# Arduino_MEGA_shield.net
KiCad netlist of a schematic drawn in EAGLE
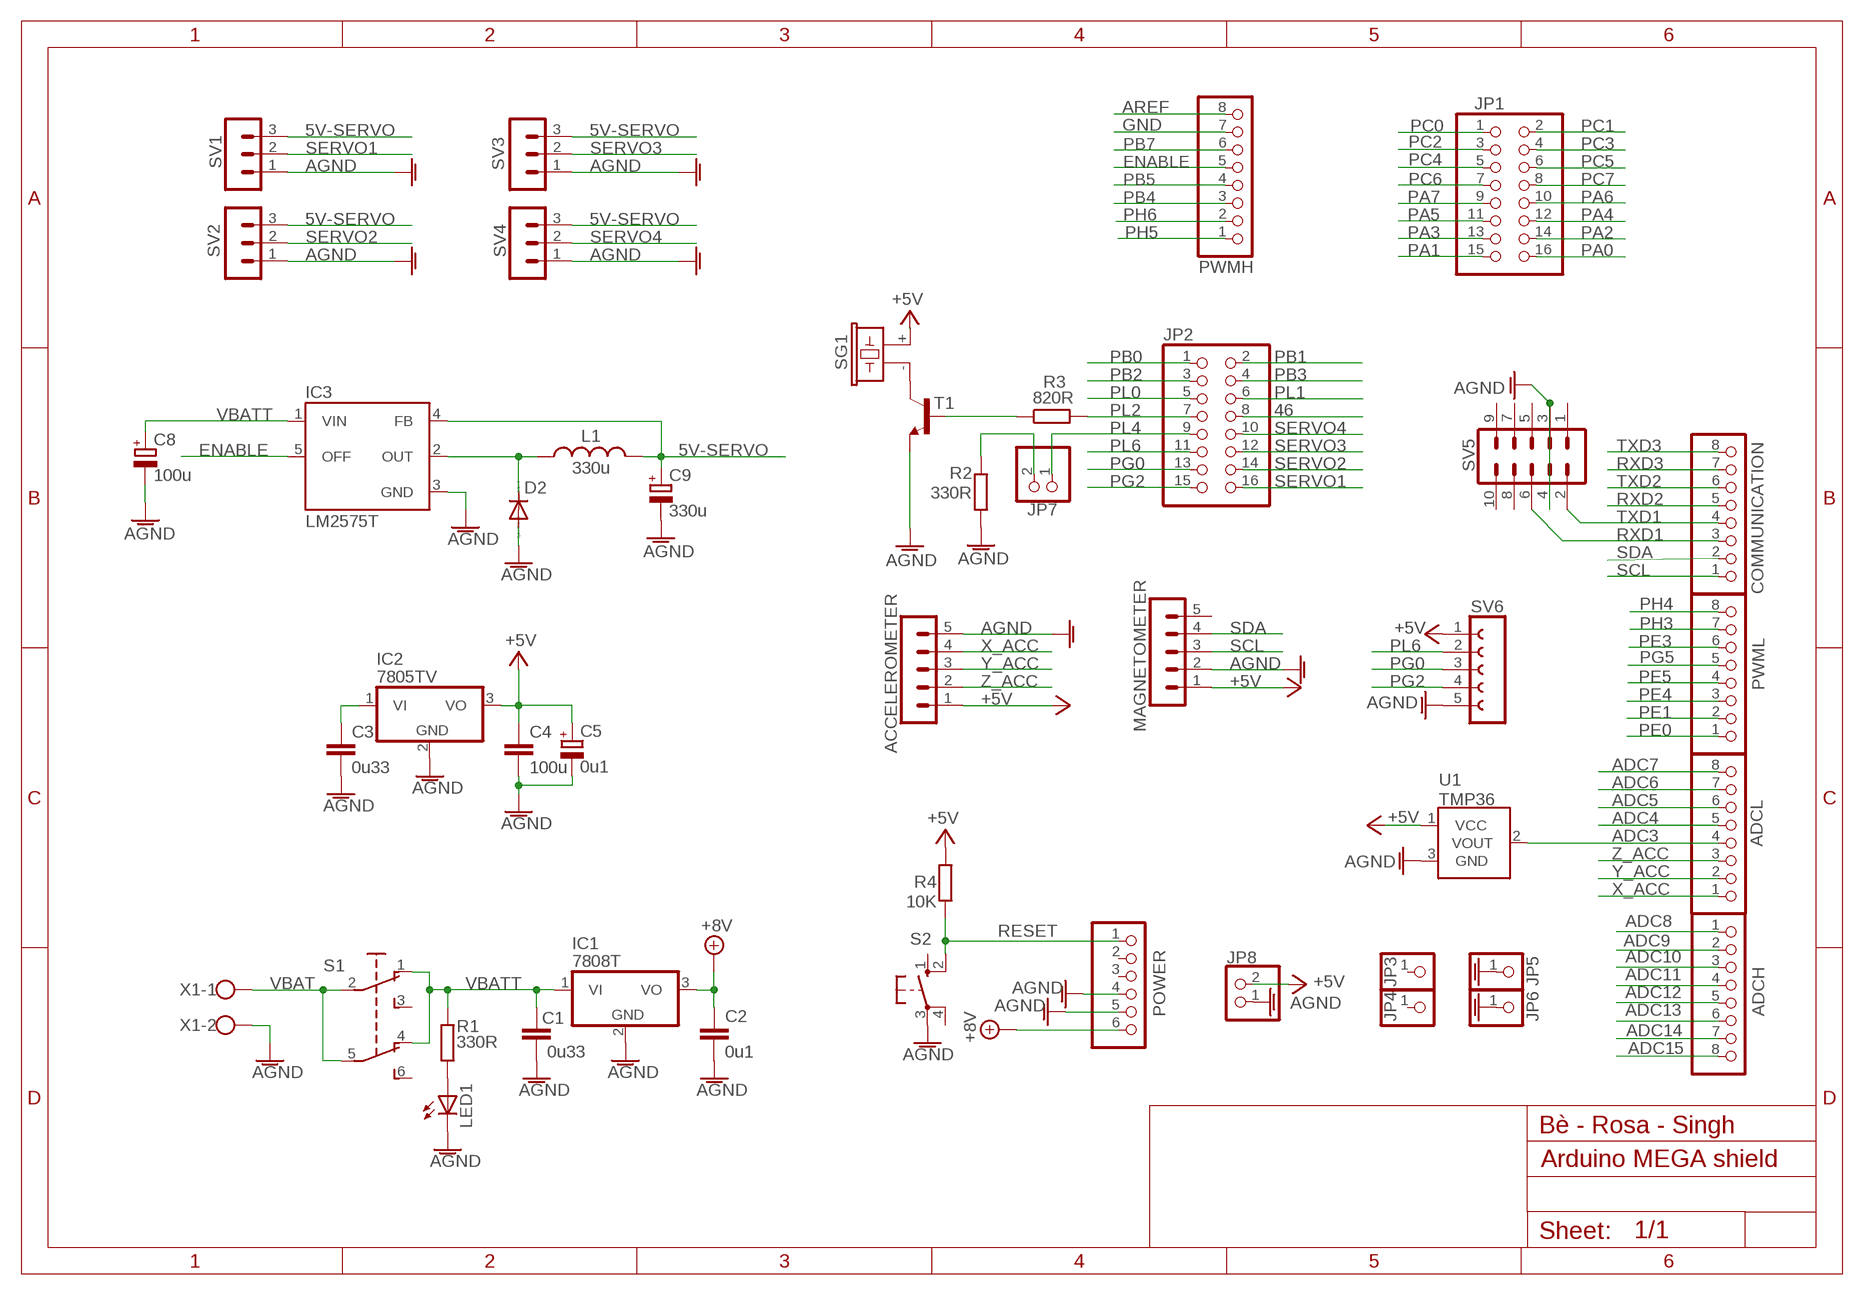
[diagram p0: schematic, sheet 1]

(export (version "E")
  (design (tool "Eeschema 10.0.6"))
  (components
    (comp (ref "ACCELEROMETER")
      (value "MA05-1")
      (footprint "eagle-import:MA05-1")
      (libsource (lib "eagle-import") (part "MA05-1"))
    )
    (comp (ref "ADCH")
      (value "PINHD-1X8")
      (footprint "eagle-import:1X08")
      (libsource (lib "eagle-import") (part "PINHD-1X8"))
    )
    (comp (ref "ADCL")
      (value "PINHD-1X8")
      (footprint "eagle-import:1X08")
      (libsource (lib "eagle-import") (part "PINHD-1X8"))
    )
    (comp (ref "C1")
      (value "0u33")
      (footprint "eagle-import:C050-035X075")
      (libsource (lib "eagle-import") (part "C-EU050-035X075"))
    )
    (comp (ref "C2")
      (value "0u1")
      (footprint "eagle-import:C050-035X075")
      (libsource (lib "eagle-import") (part "C-EU050-035X075"))
    )
    (comp (ref "C3")
      (value "0u33")
      (footprint "eagle-import:C050-035X075")
      (libsource (lib "eagle-import") (part "C-EU050-035X075"))
    )
    (comp (ref "C4")
      (value "100u")
      (footprint "eagle-import:C050-035X075")
      (libsource (lib "eagle-import") (part "C-EU050-035X075"))
    )
    (comp (ref "C5")
      (value "0u1")
      (footprint "eagle-import:E2,5-7")
      (libsource (lib "eagle-import") (part "CPOL-EUE2.5-7"))
    )
    (comp (ref "C8")
      (value "100u")
      (footprint "eagle-import:E3,5-8")
      (libsource (lib "eagle-import") (part "CPOL-EUE3.5-8"))
    )
    (comp (ref "C9")
      (value "330u")
      (footprint "eagle-import:E3,5-8")
      (libsource (lib "eagle-import") (part "CPOL-EUE3.5-8"))
    )
    (comp (ref "COMMUNICATION")
      (value "PINHD-1X8")
      (footprint "eagle-import:1X08")
      (libsource (lib "eagle-import") (part "PINHD-1X8"))
    )
    (comp (ref "D2")
      (value "1N5819")
      (footprint "eagle-import:DO35-10")
      (libsource (lib "eagle-import") (part "BA221"))
    )
    (comp (ref "IC1")
      (value "7808T")
      (footprint "eagle-import:TO220H")
      (libsource (lib "eagle-import") (part "78T08"))
    )
    (comp (ref "IC2")
      (value "7805TV")
      (footprint "eagle-import:TO220V")
      (libsource (lib "eagle-import") (part "78TV05"))
    )
    (comp (ref "IC3")
      (value "LM2575T")
      (footprint "eagle-import:TO220-5")
      (libsource (lib "eagle-import") (part "LM2575T"))
    )
    (comp (ref "JP1")
      (value "PINHD-2X8")
      (footprint "eagle-import:2X08")
      (libsource (lib "eagle-import") (part "PINHD-2X8"))
    )
    (comp (ref "JP2")
      (value "PINHD-2X8")
      (footprint "eagle-import:2X08")
      (libsource (lib "eagle-import") (part "PINHD-2X8"))
    )
    (comp (ref "JP3")
      (value "PINHD-1X1")
      (footprint "eagle-import:1X01")
      (libsource (lib "eagle-import") (part "PINHD-1X1"))
    )
    (comp (ref "JP4")
      (value "PINHD-1X1")
      (footprint "eagle-import:1X01")
      (libsource (lib "eagle-import") (part "PINHD-1X1"))
    )
    (comp (ref "JP5")
      (value "PINHD-1X1")
      (footprint "eagle-import:1X01")
      (libsource (lib "eagle-import") (part "PINHD-1X1"))
    )
    (comp (ref "JP6")
      (value "PINHD-1X1")
      (footprint "eagle-import:1X01")
      (libsource (lib "eagle-import") (part "PINHD-1X1"))
    )
    (comp (ref "JP7")
      (value "PINHD-1X2")
      (footprint "eagle-import:1X02")
      (libsource (lib "eagle-import") (part "PINHD-1X2"))
    )
    (comp (ref "JP8")
      (value "PINHD-1X2")
      (footprint "eagle-import:1X02")
      (libsource (lib "eagle-import") (part "PINHD-1X2"))
    )
    (comp (ref "L1")
      (value "330u")
      (footprint "eagle-import:AXIAL-0.6")
      (libsource (lib "eagle-import") (part "INDUCTORAXIAL-0.6"))
    )
    (comp (ref "LED1")
      (value "LED5MM")
      (footprint "eagle-import:LED5MM")
      (libsource (lib "eagle-import") (part "LED5MM"))
    )
    (comp (ref "MAGNETOMETER")
      (value "MA05-1")
      (footprint "eagle-import:MA05-1")
      (libsource (lib "eagle-import") (part "MA05-1"))
    )
    (comp (ref "POWER")
      (value "PINHD-1X6")
      (footprint "eagle-import:1X06")
      (libsource (lib "eagle-import") (part "PINHD-1X6"))
    )
    (comp (ref "PWMH")
      (value "PINHD-1X8")
      (footprint "eagle-import:1X08")
      (libsource (lib "eagle-import") (part "PINHD-1X8"))
    )
    (comp (ref "PWML")
      (value "PINHD-1X8")
      (footprint "eagle-import:1X08")
      (libsource (lib "eagle-import") (part "PINHD-1X8"))
    )
    (comp (ref "R1")
      (value "330R")
      (footprint "eagle-import:0207_10")
      (libsource (lib "eagle-import") (part "R-EU_0207/10"))
    )
    (comp (ref "R2")
      (value "330R")
      (footprint "eagle-import:0207_10")
      (libsource (lib "eagle-import") (part "R-EU_0207/10"))
    )
    (comp (ref "R3")
      (value "820R")
      (footprint "eagle-import:0207_10")
      (libsource (lib "eagle-import") (part "R-EU_0207/10"))
    )
    (comp (ref "R4")
      (value "10K")
      (footprint "eagle-import:0207_10")
      (libsource (lib "eagle-import") (part "R-EU_0207/10"))
    )
    (comp (ref "S1")
      (value "TL46PO")
      (footprint "eagle-import:TL4XPO")
      (libsource (lib "eagle-import") (part "TL46PO"))
    )
    (comp (ref "S2")
      (value "10-XX")
      (footprint "eagle-import:B3F-10XX")
      (fields (field (name "MPN") "B3F-1000"))
      (libsource (lib "eagle-import") (part "10-XX"))
    )
    (comp (ref "SG1")
      (value "F/CM12P")
      (footprint "eagle-import:F_CM12P")
      (libsource (lib "eagle-import") (part "F/CM12P"))
    )
    (comp (ref "SV1")
      (value "MA03-1")
      (footprint "eagle-import:MA03-1")
      (libsource (lib "eagle-import") (part "MA03-1"))
    )
    (comp (ref "SV2")
      (value "MA03-1")
      (footprint "eagle-import:MA03-1")
      (libsource (lib "eagle-import") (part "MA03-1"))
    )
    (comp (ref "SV3")
      (value "MA03-1")
      (footprint "eagle-import:MA03-1")
      (libsource (lib "eagle-import") (part "MA03-1"))
    )
    (comp (ref "SV4")
      (value "MA03-1")
      (footprint "eagle-import:MA03-1")
      (libsource (lib "eagle-import") (part "MA03-1"))
    )
    (comp (ref "SV5")
      (value "MA05-2")
      (footprint "eagle-import:MA05-2")
      (libsource (lib "eagle-import") (part "MA05-2"))
    )
    (comp (ref "SV6")
      (value "FE05-1")
      (footprint "eagle-import:FE05-1")
      (libsource (lib "eagle-import") (part "FE05-1"))
    )
    (comp (ref "T1")
      (value "BC547A-NPN-TO92-CBE")
      (footprint "eagle-import:TO92-CBE")
      (libsource (lib "eagle-import") (part "-NPN-TO92-CBEBC547A"))
    )
    (comp (ref "U1")
      (value "TMP36")
      (footprint "eagle-import:TO-92")
      (libsource (lib "eagle-import") (part "TMP36GT9"))
    )
    (comp (ref "X1")
      (value "W237-102")
      (footprint "eagle-import:W237-102")
      (fields (field (name "MPN") "237-102"))
      (libsource (lib "eagle-import") (part "W237-102"))
    )
  )
  (nets
    (net (code "1") (name "+5V") (class "Default")
      (node (ref "ACCELEROMETER") (pin "1") (pinfunction "1_1") (pintype "passive"))
      (node (ref "C4") (pin "1") (pinfunction "1_1") (pintype "passive"))
      (node (ref "C5") (pin "+") (pinfunction "+_+") (pintype "passive"))
      (node (ref "IC2") (pin "3") (pinfunction "VO_3") (pintype "passive"))
      (node (ref "JP8") (pin "2") (pinfunction "2_2") (pintype "passive"))
      (node (ref "MAGNETOMETER") (pin "1") (pinfunction "1_1") (pintype "passive"))
      (node (ref "R4") (pin "2") (pinfunction "2_2") (pintype "passive"))
      (node (ref "SG1") (pin "+") (pinfunction "1_+") (pintype "passive"))
      (node (ref "SV6") (pin "1") (pinfunction "1_1") (pintype "passive"))
      (node (ref "U1") (pin "1") (pinfunction "VCC_1") (pintype "bidirectional"))
    )
    (net (code "2") (name "+8V") (class "Default")
      (node (ref "C2") (pin "1") (pinfunction "1_1") (pintype "passive"))
      (node (ref "IC1") (pin "3") (pinfunction "VO_3") (pintype "passive"))
      (node (ref "POWER") (pin "6") (pinfunction "6_6") (pintype "passive"))
    )
    (net (code "3") (name "/5V-SERVO") (class "Default")
      (node (ref "C9") (pin "+") (pinfunction "+_+") (pintype "passive"))
      (node (ref "IC3") (pin "4") (pinfunction "FB_4") (pintype "input"))
      (node (ref "L1") (pin "P$2") (pinfunction "2_P$2") (pintype "passive"))
      (node (ref "SV1") (pin "3") (pinfunction "3_3") (pintype "passive"))
      (node (ref "SV2") (pin "3") (pinfunction "3_3") (pintype "passive"))
      (node (ref "SV3") (pin "3") (pinfunction "3_3") (pintype "passive"))
      (node (ref "SV4") (pin "3") (pinfunction "3_3") (pintype "passive"))
    )
    (net (code "4") (name "/46") (class "Default")
      (node (ref "JP2") (pin "8") (pinfunction "8_8") (pintype "passive"))
    )
    (net (code "5") (name "/ADC3") (class "Default")
      (node (ref "ADCL") (pin "4") (pinfunction "4_4") (pintype "passive"))
      (node (ref "U1") (pin "2") (pinfunction "VOUT_2") (pintype "bidirectional"))
    )
    (net (code "6") (name "/ADC4") (class "Default")
      (node (ref "ADCL") (pin "5") (pinfunction "5_5") (pintype "passive"))
    )
    (net (code "7") (name "/ADC5") (class "Default")
      (node (ref "ADCL") (pin "6") (pinfunction "6_6") (pintype "passive"))
    )
    (net (code "8") (name "/ADC6") (class "Default")
      (node (ref "ADCL") (pin "7") (pinfunction "7_7") (pintype "passive"))
    )
    (net (code "9") (name "/ADC7") (class "Default")
      (node (ref "ADCL") (pin "8") (pinfunction "8_8") (pintype "passive"))
    )
    (net (code "10") (name "/ADC8") (class "Default")
      (node (ref "ADCH") (pin "1") (pinfunction "1_1") (pintype "passive"))
    )
    (net (code "11") (name "/ADC9") (class "Default")
      (node (ref "ADCH") (pin "2") (pinfunction "2_2") (pintype "passive"))
    )
    (net (code "12") (name "/ADC10") (class "Default")
      (node (ref "ADCH") (pin "3") (pinfunction "3_3") (pintype "passive"))
    )
    (net (code "13") (name "/ADC11") (class "Default")
      (node (ref "ADCH") (pin "4") (pinfunction "4_4") (pintype "passive"))
    )
    (net (code "14") (name "/ADC12") (class "Default")
      (node (ref "ADCH") (pin "5") (pinfunction "5_5") (pintype "passive"))
    )
    (net (code "15") (name "/ADC13") (class "Default")
      (node (ref "ADCH") (pin "6") (pinfunction "6_6") (pintype "passive"))
    )
    (net (code "16") (name "/ADC14") (class "Default")
      (node (ref "ADCH") (pin "7") (pinfunction "7_7") (pintype "passive"))
    )
    (net (code "17") (name "/ADC15") (class "Default")
      (node (ref "ADCH") (pin "8") (pinfunction "8_8") (pintype "passive"))
    )
    (net (code "18") (name "/AREF") (class "Default")
      (node (ref "PWMH") (pin "8") (pinfunction "8_8") (pintype "passive"))
    )
    (net (code "19") (name "/ENABLE") (class "Default")
      (node (ref "IC3") (pin "5") (pinfunction "OFF_5") (pintype "input"))
      (node (ref "PWMH") (pin "5") (pinfunction "5_5") (pintype "passive"))
    )
    (net (code "20") (name "/GND") (class "Default")
      (node (ref "PWMH") (pin "7") (pinfunction "7_7") (pintype "passive"))
    )
    (net (code "21") (name "/PA0") (class "Default")
      (node (ref "JP1") (pin "16") (pinfunction "16_16") (pintype "passive"))
    )
    (net (code "22") (name "/PA1") (class "Default")
      (node (ref "JP1") (pin "15") (pinfunction "15_15") (pintype "passive"))
    )
    (net (code "23") (name "/PA2") (class "Default")
      (node (ref "JP1") (pin "14") (pinfunction "14_14") (pintype "passive"))
    )
    (net (code "24") (name "/PA3") (class "Default")
      (node (ref "JP1") (pin "13") (pinfunction "13_13") (pintype "passive"))
    )
    (net (code "25") (name "/PA4") (class "Default")
      (node (ref "JP1") (pin "12") (pinfunction "12_12") (pintype "passive"))
    )
    (net (code "26") (name "/PA5") (class "Default")
      (node (ref "JP1") (pin "11") (pinfunction "11_11") (pintype "passive"))
    )
    (net (code "27") (name "/PA6") (class "Default")
      (node (ref "JP1") (pin "10") (pinfunction "10_10") (pintype "passive"))
    )
    (net (code "28") (name "/PA7") (class "Default")
      (node (ref "JP1") (pin "9") (pinfunction "9_9") (pintype "passive"))
    )
    (net (code "29") (name "/PB0") (class "Default")
      (node (ref "JP2") (pin "1") (pinfunction "1_1") (pintype "passive"))
    )
    (net (code "30") (name "/PB1") (class "Default")
      (node (ref "JP2") (pin "2") (pinfunction "2_2") (pintype "passive"))
    )
    (net (code "31") (name "/PB2") (class "Default")
      (node (ref "JP2") (pin "3") (pinfunction "3_3") (pintype "passive"))
    )
    (net (code "32") (name "/PB3") (class "Default")
      (node (ref "JP2") (pin "4") (pinfunction "4_4") (pintype "passive"))
    )
    (net (code "33") (name "/PB4") (class "Default")
      (node (ref "PWMH") (pin "3") (pinfunction "3_3") (pintype "passive"))
    )
    (net (code "34") (name "/PB5") (class "Default")
      (node (ref "PWMH") (pin "4") (pinfunction "4_4") (pintype "passive"))
    )
    (net (code "35") (name "/PB7") (class "Default")
      (node (ref "PWMH") (pin "6") (pinfunction "6_6") (pintype "passive"))
    )
    (net (code "36") (name "/PC0") (class "Default")
      (node (ref "JP1") (pin "1") (pinfunction "1_1") (pintype "passive"))
    )
    (net (code "37") (name "/PC1") (class "Default")
      (node (ref "JP1") (pin "2") (pinfunction "2_2") (pintype "passive"))
    )
    (net (code "38") (name "/PC2") (class "Default")
      (node (ref "JP1") (pin "3") (pinfunction "3_3") (pintype "passive"))
    )
    (net (code "39") (name "/PC3") (class "Default")
      (node (ref "JP1") (pin "4") (pinfunction "4_4") (pintype "passive"))
    )
    (net (code "40") (name "/PC4") (class "Default")
      (node (ref "JP1") (pin "5") (pinfunction "5_5") (pintype "passive"))
    )
    (net (code "41") (name "/PC5") (class "Default")
      (node (ref "JP1") (pin "6") (pinfunction "6_6") (pintype "passive"))
    )
    (net (code "42") (name "/PC6") (class "Default")
      (node (ref "JP1") (pin "7") (pinfunction "7_7") (pintype "passive"))
    )
    (net (code "43") (name "/PC7") (class "Default")
      (node (ref "JP1") (pin "8") (pinfunction "8_8") (pintype "passive"))
    )
    (net (code "44") (name "/PE0") (class "Default")
      (node (ref "PWML") (pin "1") (pinfunction "1_1") (pintype "passive"))
    )
    (net (code "45") (name "/PE1") (class "Default")
      (node (ref "PWML") (pin "2") (pinfunction "2_2") (pintype "passive"))
    )
    (net (code "46") (name "/PE3") (class "Default")
      (node (ref "PWML") (pin "6") (pinfunction "6_6") (pintype "passive"))
    )
    (net (code "47") (name "/PE4") (class "Default")
      (node (ref "PWML") (pin "3") (pinfunction "3_3") (pintype "passive"))
    )
    (net (code "48") (name "/PE5") (class "Default")
      (node (ref "PWML") (pin "4") (pinfunction "4_4") (pintype "passive"))
    )
    (net (code "49") (name "/PG0") (class "Default")
      (node (ref "JP2") (pin "13") (pinfunction "13_13") (pintype "passive"))
      (node (ref "SV6") (pin "3") (pinfunction "3_3") (pintype "passive"))
    )
    (net (code "50") (name "/PG2") (class "Default")
      (node (ref "JP2") (pin "15") (pinfunction "15_15") (pintype "passive"))
      (node (ref "SV6") (pin "4") (pinfunction "4_4") (pintype "passive"))
    )
    (net (code "51") (name "/PG5") (class "Default")
      (node (ref "PWML") (pin "5") (pinfunction "5_5") (pintype "passive"))
    )
    (net (code "52") (name "/PH3") (class "Default")
      (node (ref "PWML") (pin "7") (pinfunction "7_7") (pintype "passive"))
    )
    (net (code "53") (name "/PH4") (class "Default")
      (node (ref "PWML") (pin "8") (pinfunction "8_8") (pintype "passive"))
    )
    (net (code "54") (name "/PH5") (class "Default")
      (node (ref "PWMH") (pin "1") (pinfunction "1_1") (pintype "passive"))
    )
    (net (code "55") (name "/PH6") (class "Default")
      (node (ref "PWMH") (pin "2") (pinfunction "2_2") (pintype "passive"))
    )
    (net (code "56") (name "/PL0") (class "Default")
      (node (ref "JP2") (pin "5") (pinfunction "5_5") (pintype "passive"))
    )
    (net (code "57") (name "/PL1") (class "Default")
      (node (ref "JP2") (pin "6") (pinfunction "6_6") (pintype "passive"))
    )
    (net (code "58") (name "/PL2") (class "Default")
      (node (ref "JP2") (pin "7") (pinfunction "7_7") (pintype "passive"))
      (node (ref "R3") (pin "2") (pinfunction "2_2") (pintype "passive"))
    )
    (net (code "59") (name "/PL4") (class "Default")
      (node (ref "JP2") (pin "9") (pinfunction "9_9") (pintype "passive"))
      (node (ref "JP7") (pin "1") (pinfunction "1_1") (pintype "passive"))
    )
    (net (code "60") (name "/PL6") (class "Default")
      (node (ref "JP2") (pin "11") (pinfunction "11_11") (pintype "passive"))
      (node (ref "SV6") (pin "2") (pinfunction "2_2") (pintype "passive"))
    )
    (net (code "61") (name "/RESET") (class "Default")
      (node (ref "POWER") (pin "1") (pinfunction "1_1") (pintype "passive"))
      (node (ref "R4") (pin "1") (pinfunction "1_1") (pintype "passive"))
      (node (ref "S2") (pin "2") (pinfunction "S1_2") (pintype "passive"))
    )
    (net (code "62") (name "/RXD1") (class "Default")
      (node (ref "COMMUNICATION") (pin "3") (pinfunction "3_3") (pintype "passive"))
      (node (ref "SV5") (pin "6") (pinfunction "6_6") (pintype "passive"))
    )
    (net (code "63") (name "/RXD2") (class "Default")
      (node (ref "COMMUNICATION") (pin "5") (pinfunction "5_5") (pintype "passive"))
    )
    (net (code "64") (name "/RXD3") (class "Default")
      (node (ref "COMMUNICATION") (pin "7") (pinfunction "7_7") (pintype "passive"))
    )
    (net (code "65") (name "/SCL") (class "Default")
      (node (ref "COMMUNICATION") (pin "1") (pinfunction "1_1") (pintype "passive"))
      (node (ref "MAGNETOMETER") (pin "3") (pinfunction "3_3") (pintype "passive"))
    )
    (net (code "66") (name "/SDA") (class "Default")
      (node (ref "COMMUNICATION") (pin "2") (pinfunction "2_2") (pintype "passive"))
      (node (ref "MAGNETOMETER") (pin "4") (pinfunction "4_4") (pintype "passive"))
    )
    (net (code "67") (name "/SERVO1") (class "Default")
      (node (ref "JP2") (pin "16") (pinfunction "16_16") (pintype "passive"))
      (node (ref "SV1") (pin "2") (pinfunction "2_2") (pintype "passive"))
    )
    (net (code "68") (name "/SERVO2") (class "Default")
      (node (ref "JP2") (pin "14") (pinfunction "14_14") (pintype "passive"))
      (node (ref "SV2") (pin "2") (pinfunction "2_2") (pintype "passive"))
    )
    (net (code "69") (name "/SERVO3") (class "Default")
      (node (ref "JP2") (pin "12") (pinfunction "12_12") (pintype "passive"))
      (node (ref "SV3") (pin "2") (pinfunction "2_2") (pintype "passive"))
    )
    (net (code "70") (name "/SERVO4") (class "Default")
      (node (ref "JP2") (pin "10") (pinfunction "10_10") (pintype "passive"))
      (node (ref "SV4") (pin "2") (pinfunction "2_2") (pintype "passive"))
    )
    (net (code "71") (name "/TXD1") (class "Default")
      (node (ref "COMMUNICATION") (pin "4") (pinfunction "4_4") (pintype "passive"))
      (node (ref "SV5") (pin "2") (pinfunction "2_2") (pintype "passive"))
    )
    (net (code "72") (name "/TXD2") (class "Default")
      (node (ref "COMMUNICATION") (pin "6") (pinfunction "6_6") (pintype "passive"))
    )
    (net (code "73") (name "/TXD3") (class "Default")
      (node (ref "COMMUNICATION") (pin "8") (pinfunction "8_8") (pintype "passive"))
    )
    (net (code "74") (name "/VBAT") (class "Default")
      (node (ref "S1") (pin "2") (pinfunction "P_2") (pintype "passive"))
      (node (ref "S1") (pin "5") (pinfunction "P1_5") (pintype "passive"))
      (node (ref "X1") (pin "1") (pinfunction "KL_1") (pintype "passive"))
    )
    (net (code "75") (name "/VBATT") (class "Default")
      (node (ref "C1") (pin "1") (pinfunction "1_1") (pintype "passive"))
      (node (ref "C8") (pin "+") (pinfunction "+_+") (pintype "passive"))
      (node (ref "IC1") (pin "1") (pinfunction "VI_1") (pintype "input"))
      (node (ref "IC3") (pin "1") (pinfunction "VIN_1") (pintype "power_in"))
      (node (ref "R1") (pin "2") (pinfunction "2_2") (pintype "passive"))
      (node (ref "S1") (pin "1") (pinfunction "O_1") (pintype "passive"))
      (node (ref "S1") (pin "4") (pinfunction "O1_4") (pintype "passive"))
    )
    (net (code "76") (name "/X_ACC") (class "Default")
      (node (ref "ACCELEROMETER") (pin "4") (pinfunction "4_4") (pintype "passive"))
      (node (ref "ADCL") (pin "1") (pinfunction "1_1") (pintype "passive"))
    )
    (net (code "77") (name "/Y_ACC") (class "Default")
      (node (ref "ACCELEROMETER") (pin "3") (pinfunction "3_3") (pintype "passive"))
      (node (ref "ADCL") (pin "2") (pinfunction "2_2") (pintype "passive"))
    )
    (net (code "78") (name "/Z_ACC") (class "Default")
      (node (ref "ACCELEROMETER") (pin "2") (pinfunction "2_2") (pintype "passive"))
      (node (ref "ADCL") (pin "3") (pinfunction "3_3") (pintype "passive"))
    )
    (net (code "79") (name "AGND") (class "Default")
      (node (ref "ACCELEROMETER") (pin "5") (pinfunction "5_5") (pintype "passive"))
      (node (ref "C1") (pin "2") (pinfunction "2_2") (pintype "passive"))
      (node (ref "C2") (pin "2") (pinfunction "2_2") (pintype "passive"))
      (node (ref "C3") (pin "2") (pinfunction "2_2") (pintype "passive"))
      (node (ref "C4") (pin "2") (pinfunction "2_2") (pintype "passive"))
      (node (ref "C5") (pin "-") (pinfunction "-_-") (pintype "passive"))
      (node (ref "C8") (pin "-") (pinfunction "-_-") (pintype "passive"))
      (node (ref "C9") (pin "-") (pinfunction "-_-") (pintype "passive"))
      (node (ref "D2") (pin "A") (pinfunction "A_A") (pintype "passive"))
      (node (ref "IC1") (pin "2") (pinfunction "GND_2") (pintype "passive"))
      (node (ref "IC2") (pin "2") (pinfunction "GND_2") (pintype "passive"))
      (node (ref "IC3") (pin "3") (pinfunction "GND_3") (pintype "power_in"))
      (node (ref "JP5") (pin "1") (pinfunction "1_1") (pintype "passive"))
      (node (ref "JP6") (pin "1") (pinfunction "1_1") (pintype "passive"))
      (node (ref "JP8") (pin "1") (pinfunction "1_1") (pintype "passive"))
      (node (ref "LED1") (pin "K") (pinfunction "C_K") (pintype "passive"))
      (node (ref "MAGNETOMETER") (pin "2") (pinfunction "2_2") (pintype "passive"))
      (node (ref "POWER") (pin "4") (pinfunction "4_4") (pintype "passive"))
      (node (ref "POWER") (pin "5") (pinfunction "5_5") (pintype "passive"))
      (node (ref "R2") (pin "2") (pinfunction "2_2") (pintype "passive"))
      (node (ref "S2") (pin "3") (pinfunction "P_3") (pintype "passive"))
      (node (ref "SV1") (pin "1") (pinfunction "1_1") (pintype "passive"))
      (node (ref "SV2") (pin "1") (pinfunction "1_1") (pintype "passive"))
      (node (ref "SV3") (pin "1") (pinfunction "1_1") (pintype "passive"))
      (node (ref "SV4") (pin "1") (pinfunction "1_1") (pintype "passive"))
      (node (ref "SV5") (pin "3") (pinfunction "3_3") (pintype "passive"))
      (node (ref "SV5") (pin "4") (pinfunction "4_4") (pintype "passive"))
      (node (ref "SV6") (pin "5") (pinfunction "5_5") (pintype "passive"))
      (node (ref "T1") (pin "E") (pinfunction "E_E") (pintype "passive"))
      (node (ref "U1") (pin "3") (pinfunction "GND_3") (pintype "bidirectional"))
      (node (ref "X1") (pin "2") (pinfunction "KL_2") (pintype "passive"))
    )
    (net (code "80") (name "Net-(IC2-VI)") (class "Default")
      (node (ref "C3") (pin "1") (pinfunction "1_1") (pintype "passive"))
      (node (ref "IC2") (pin "1") (pinfunction "VI_1") (pintype "input"))
    )
    (net (code "81") (name "Net-(IC3-OUT)") (class "Default")
      (node (ref "D2") (pin "C") (pinfunction "C_C") (pintype "passive"))
      (node (ref "IC3") (pin "2") (pinfunction "OUT_2") (pintype "output"))
      (node (ref "L1") (pin "P$1") (pinfunction "1_P$1") (pintype "passive"))
    )
    (net (code "82") (name "Net-(JP7-Pad2)") (class "Default")
      (node (ref "JP7") (pin "2") (pinfunction "2_2") (pintype "passive"))
      (node (ref "R2") (pin "1") (pinfunction "1_1") (pintype "passive"))
    )
    (net (code "83") (name "Net-(LED1-PadA)") (class "Default")
      (node (ref "LED1") (pin "A") (pinfunction "A_A") (pintype "passive"))
      (node (ref "R1") (pin "1") (pinfunction "1_1") (pintype "passive"))
    )
    (net (code "84") (name "Net-(R3-Pad1)") (class "Default")
      (node (ref "R3") (pin "1") (pinfunction "1_1") (pintype "passive"))
      (node (ref "T1") (pin "B") (pinfunction "B_B") (pintype "passive"))
    )
    (net (code "85") (name "Net-(SG1-2)") (class "Default")
      (node (ref "SG1") (pin "-") (pinfunction "2_-") (pintype "passive"))
      (node (ref "T1") (pin "C") (pinfunction "C_C") (pintype "passive"))
    )
    (net (code "86") (name "unconnected-(JP3-Pad1)") (class "Default")
      (node (ref "JP3") (pin "1") (pinfunction "1_1") (pintype "passive"))
    )
    (net (code "87") (name "unconnected-(JP4-Pad1)") (class "Default")
      (node (ref "JP4") (pin "1") (pinfunction "1_1") (pintype "passive"))
    )
    (net (code "88") (name "unconnected-(MAGNETOMETER-Pad5)") (class "Default")
      (node (ref "MAGNETOMETER") (pin "5") (pinfunction "5_5") (pintype "passive"))
    )
    (net (code "89") (name "unconnected-(POWER-Pad2)") (class "Default")
      (node (ref "POWER") (pin "2") (pinfunction "2_2") (pintype "passive"))
    )
    (net (code "90") (name "unconnected-(POWER-Pad3)") (class "Default")
      (node (ref "POWER") (pin "3") (pinfunction "3_3") (pintype "passive"))
    )
    (net (code "91") (name "unconnected-(S1-S-Pad3)") (class "Default")
      (node (ref "S1") (pin "3") (pinfunction "S_3") (pintype "passive"))
    )
    (net (code "92") (name "unconnected-(S1-S1-Pad6)") (class "Default")
      (node (ref "S1") (pin "6") (pinfunction "S1_6") (pintype "passive"))
    )
    (net (code "93") (name "unconnected-(S2-P1-Pad4)") (class "Default")
      (node (ref "S2") (pin "4") (pinfunction "P1_4") (pintype "passive"))
    )
    (net (code "94") (name "unconnected-(S2-S-Pad1)") (class "Default")
      (node (ref "S2") (pin "1") (pinfunction "S_1") (pintype "passive"))
    )
    (net (code "95") (name "unconnected-(SV5-Pad1)") (class "Default")
      (node (ref "SV5") (pin "1") (pinfunction "1_1") (pintype "passive"))
    )
    (net (code "96") (name "unconnected-(SV5-Pad5)") (class "Default")
      (node (ref "SV5") (pin "5") (pinfunction "5_5") (pintype "passive"))
    )
    (net (code "97") (name "unconnected-(SV5-Pad7)") (class "Default")
      (node (ref "SV5") (pin "7") (pinfunction "7_7") (pintype "passive"))
    )
    (net (code "98") (name "unconnected-(SV5-Pad8)") (class "Default")
      (node (ref "SV5") (pin "8") (pinfunction "8_8") (pintype "passive"))
    )
    (net (code "99") (name "unconnected-(SV5-Pad9)") (class "Default")
      (node (ref "SV5") (pin "9") (pinfunction "9_9") (pintype "passive"))
    )
    (net (code "100") (name "unconnected-(SV5-Pad10)") (class "Default")
      (node (ref "SV5") (pin "10") (pinfunction "10_10") (pintype "passive"))
    )
  )
)
